# Connectors.net
KiCad netlist of a schematic drawn in Altium Designer
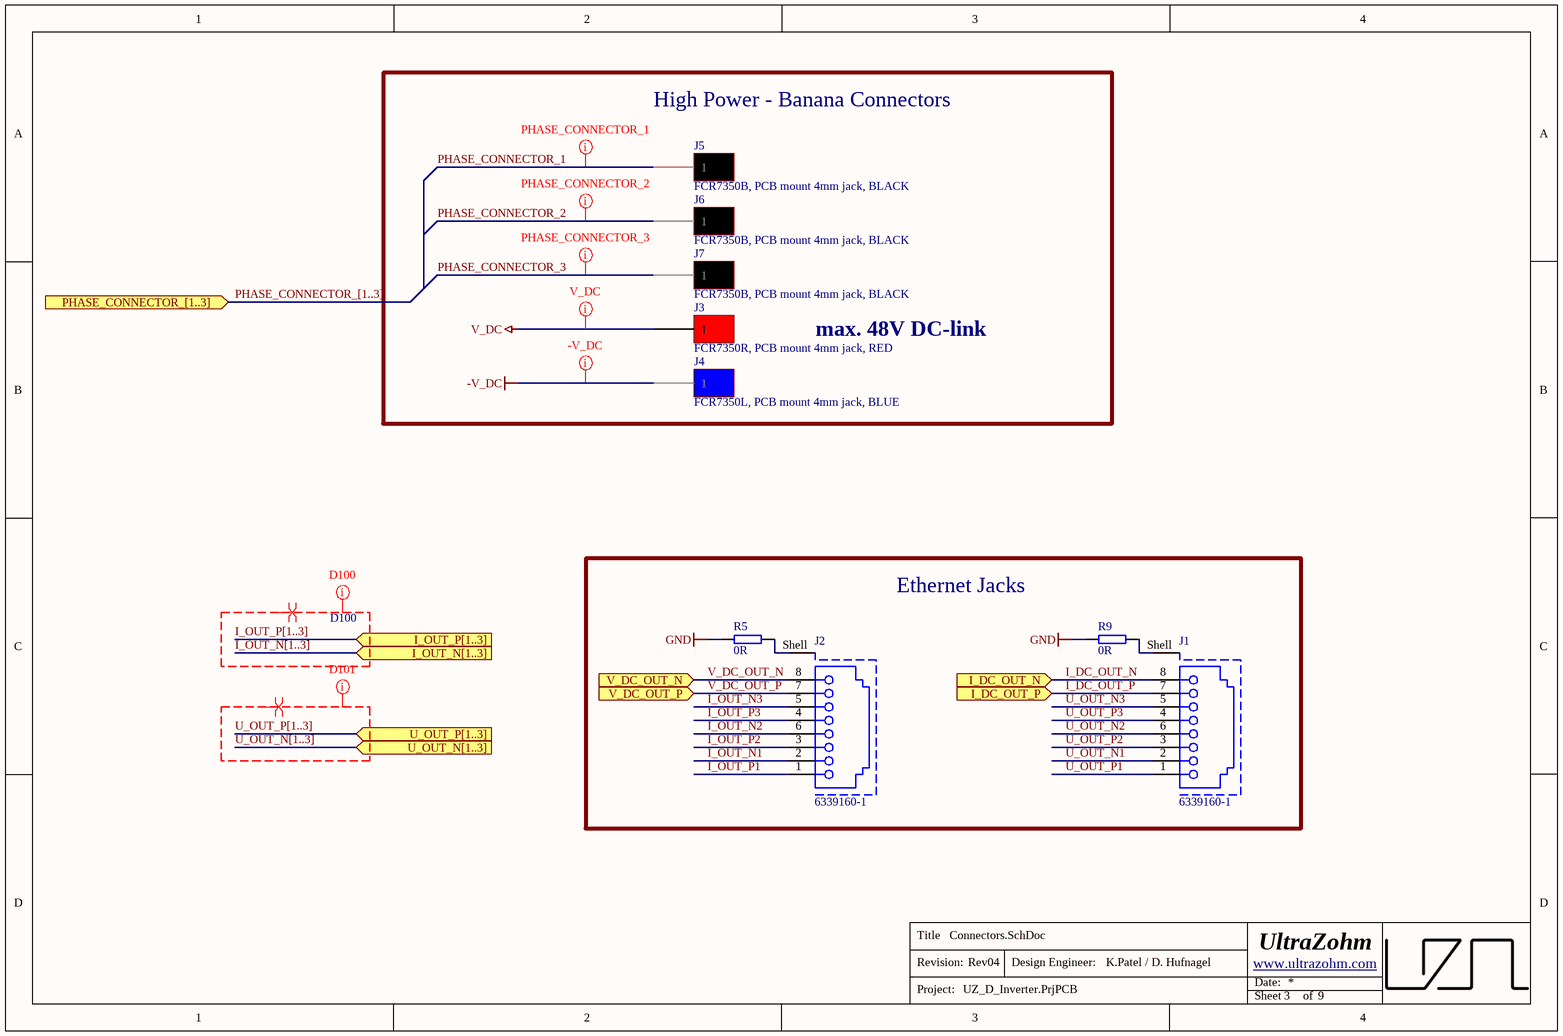
[diagram p0: Connectors.SchDoc]

(export (version "E")
  (design (tool "Eeschema 10.0.6"))
  (components
    (comp (ref "J1")
      (value "6339160-1")
      (footprint "634008149821")
      (fields
        (field (name "MANUFACTURER") "TE Connectivity")
        (field (name "LCSC PART NUMBER") "C125076")
        (field (name "CREATED FROM") "NDiringer")
      )
      (libsource (lib "user") (part "634008149821"))
    )
    (comp (ref "J2")
      (value "6339160-1")
      (footprint "634008149821")
      (fields
        (field (name "MANUFACTURER") "TE Connectivity")
        (field (name "LCSC PART NUMBER") "C125076")
        (field (name "CREATED FROM") "NDiringer")
      )
      (libsource (lib "user") (part "634008149821"))
    )
    (comp (ref "J3")
      (value "FCR7350R, PCB mount 4mm jack, RED")
      (footprint "FCR7350")
      (description "FCR7350B, 1000V, 24A, RED")
      (fields
        (field (name "MANUFACTURER PART NUMBER") "FCR7350R")
        (field (name "MANUFACTURER") "Cliff")
        (field (name "CREATED FROM") "DHufnagel")
      )
      (libsource (lib "user") (part "FCR7350R"))
    )
    (comp (ref "J4")
      (value "FCR7350L, PCB mount 4mm jack, BLUE")
      (footprint "FCR7350")
      (description "FCR7350B, 1000V, 24A, BLUE")
      (fields
        (field (name "MANUFACTURER PART NUMBER") "FCR7350L")
        (field (name "MANUFACTURER") "Cliff")
        (field (name "CREATED FROM") "DHufnagel")
      )
      (libsource (lib "user") (part "FCR7350L"))
    )
    (comp (ref "J5")
      (value "FCR7350B, PCB mount 4mm jack, BLACK")
      (footprint "FCR7350")
      (description "FCR7350B, 1000V, 24A, BLACK")
      (fields
        (field (name "MANUFACTURER PART NUMBER") "FCR7350B")
        (field (name "MANUFACTURER") "Cliff")
        (field (name "CREATED FROM") "DHufnagel")
      )
      (libsource (lib "user") (part "FCR7350B"))
    )
    (comp (ref "J6")
      (value "FCR7350B, PCB mount 4mm jack, BLACK")
      (footprint "FCR7350")
      (description "FCR7350B, 1000V, 24A, BLACK")
      (fields
        (field (name "MANUFACTURER PART NUMBER") "FCR7350B")
        (field (name "MANUFACTURER") "Cliff")
        (field (name "CREATED FROM") "DHufnagel")
      )
      (libsource (lib "user") (part "FCR7350B"))
    )
    (comp (ref "J7")
      (value "FCR7350B, PCB mount 4mm jack, BLACK")
      (footprint "FCR7350")
      (description "FCR7350B, 1000V, 24A, BLACK")
      (fields
        (field (name "MANUFACTURER PART NUMBER") "FCR7350B")
        (field (name "MANUFACTURER") "Cliff")
        (field (name "CREATED FROM") "DHufnagel")
      )
      (libsource (lib "user") (part "FCR7350B"))
    )
    (comp (ref "R5")
      (value "0R")
      (footprint "RES 0603_1608")
      (description "SMD resistor E24 series")
      (fields
        (field (name "MANUFACTURER PART NUMBER") "RC0603JR-070RL")
        (field (name "MANUFACTURER") "YAGEO")
        (field (name "CREATED FROM") "MGremer")
      )
      (libsource (lib "user") (part "Resistor"))
    )
    (comp (ref "R9")
      (value "0R")
      (footprint "RES 0603_1608")
      (description "SMD resistor E24 series")
      (fields
        (field (name "MANUFACTURER PART NUMBER") "RC0603JR-070RL")
        (field (name "MANUFACTURER") "YAGEO")
        (field (name "CREATED FROM") "MGremer")
      )
      (libsource (lib "user") (part "Resistor"))
    )
  )
  (nets
    (net (code "1") (name "-V_DC") (class "Default")
      (node (ref "J4") (pin "1") (pinfunction "1_1") (pintype "passive"))
    )
    (net (code "2") (name "/I_DC_OUT_N") (class "Default")
      (node (ref "J1") (pin "8") (pinfunction "8_8") (pintype "passive"))
    )
    (net (code "3") (name "/I_DC_OUT_P") (class "Default")
      (node (ref "J1") (pin "7") (pinfunction "7_7") (pintype "passive"))
    )
    (net (code "4") (name "/I_OUT_N1") (class "Default")
      (node (ref "J2") (pin "2") (pinfunction "2_2") (pintype "passive"))
    )
    (net (code "5") (name "/I_OUT_N2") (class "Default")
      (node (ref "J2") (pin "6") (pinfunction "6_6") (pintype "passive"))
    )
    (net (code "6") (name "/I_OUT_N3") (class "Default")
      (node (ref "J2") (pin "5") (pinfunction "5_5") (pintype "passive"))
    )
    (net (code "8") (name "/I_OUT_P1") (class "Default")
      (node (ref "J2") (pin "1") (pinfunction "1_1") (pintype "passive"))
    )
    (net (code "9") (name "/I_OUT_P2") (class "Default")
      (node (ref "J2") (pin "3") (pinfunction "3_3") (pintype "passive"))
    )
    (net (code "10") (name "/I_OUT_P3") (class "Default")
      (node (ref "J2") (pin "4") (pinfunction "4_4") (pintype "passive"))
    )
    (net (code "12") (name "/PHASE_CONNECTOR_1") (class "Default")
      (node (ref "J5") (pin "1") (pinfunction "1_1") (pintype "passive"))
    )
    (net (code "13") (name "/PHASE_CONNECTOR_2") (class "Default")
      (node (ref "J6") (pin "1") (pinfunction "1_1") (pintype "passive"))
    )
    (net (code "14") (name "/PHASE_CONNECTOR_3") (class "Default")
      (node (ref "J7") (pin "1") (pinfunction "1_1") (pintype "passive"))
    )
    (net (code "16") (name "/U_OUT_N1") (class "Default")
      (node (ref "J1") (pin "2") (pinfunction "2_2") (pintype "passive"))
    )
    (net (code "17") (name "/U_OUT_N2") (class "Default")
      (node (ref "J1") (pin "6") (pinfunction "6_6") (pintype "passive"))
    )
    (net (code "18") (name "/U_OUT_N3") (class "Default")
      (node (ref "J1") (pin "5") (pinfunction "5_5") (pintype "passive"))
    )
    (net (code "20") (name "/U_OUT_P1") (class "Default")
      (node (ref "J1") (pin "1") (pinfunction "1_1") (pintype "passive"))
    )
    (net (code "21") (name "/U_OUT_P2") (class "Default")
      (node (ref "J1") (pin "3") (pinfunction "3_3") (pintype "passive"))
    )
    (net (code "22") (name "/U_OUT_P3") (class "Default")
      (node (ref "J1") (pin "4") (pinfunction "4_4") (pintype "passive"))
    )
    (net (code "24") (name "/V_DC_OUT_N") (class "Default")
      (node (ref "J2") (pin "8") (pinfunction "8_8") (pintype "passive"))
    )
    (net (code "25") (name "/V_DC_OUT_P") (class "Default")
      (node (ref "J2") (pin "7") (pinfunction "7_7") (pintype "passive"))
    )
    (net (code "26") (name "GND") (class "Default")
      (node (ref "R5") (pin "1") (pinfunction "1_1") (pintype "passive"))
      (node (ref "R9") (pin "1") (pinfunction "1_1") (pintype "passive"))
    )
    (net (code "27") (name "Net-(J1-PadShell)") (class "Default")
      (node (ref "J1") (pin "Shell") (pinfunction "Shell_Shell") (pintype "passive"))
      (node (ref "R9") (pin "2") (pinfunction "2_2") (pintype "passive"))
    )
    (net (code "28") (name "Net-(J2-PadShell)") (class "Default")
      (node (ref "J2") (pin "Shell") (pinfunction "Shell_Shell") (pintype "passive"))
      (node (ref "R5") (pin "2") (pinfunction "2_2") (pintype "passive"))
    )
    (net (code "29") (name "V_DC") (class "Default")
      (node (ref "J3") (pin "1") (pinfunction "1_1") (pintype "passive"))
    )
  )
)
